# ADC.net
KiCad netlist of a schematic drawn in Altium Designer
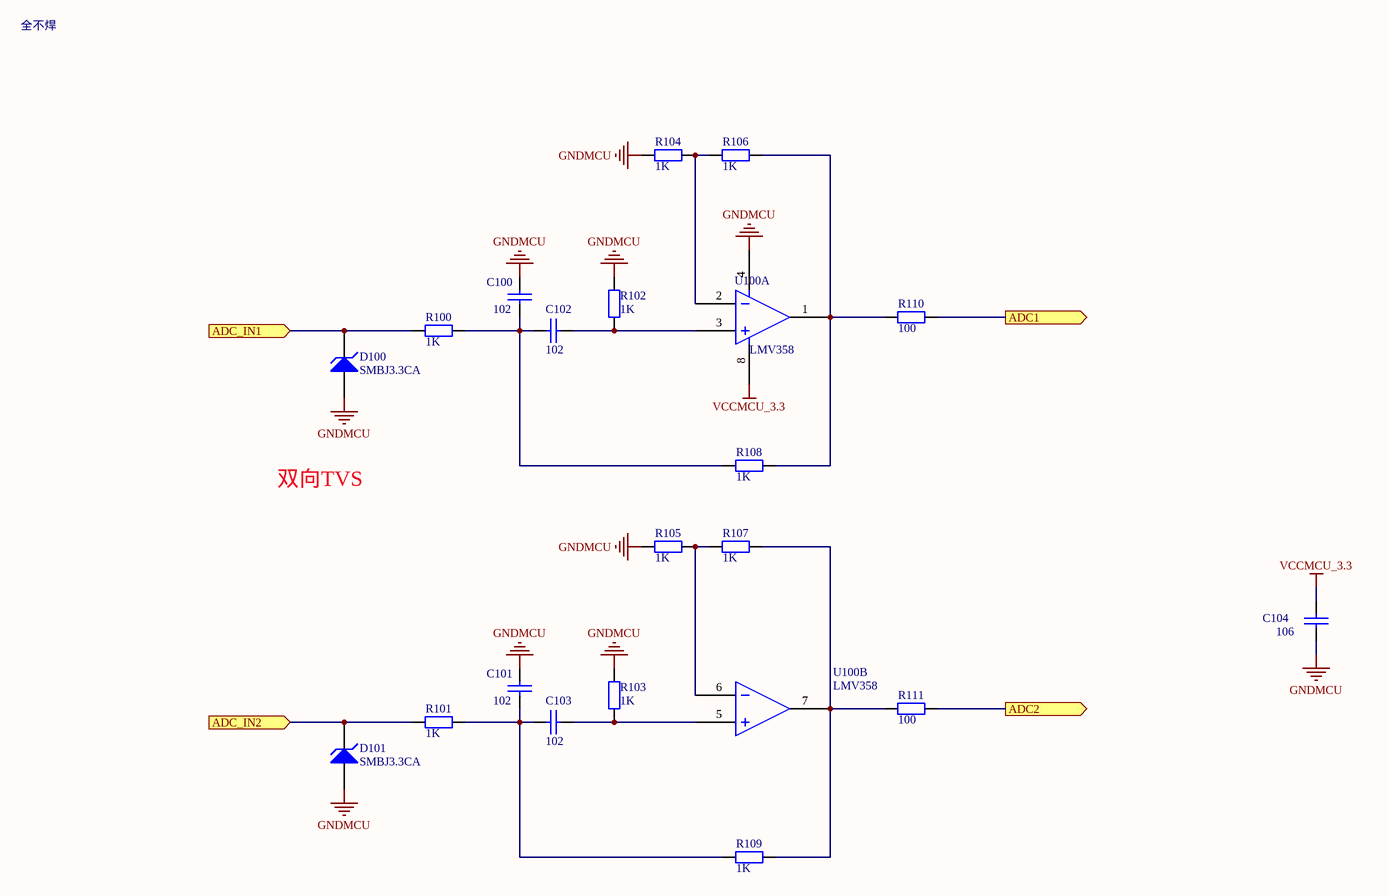
[diagram p0: ADC.SchDoc]

(export (version "E")
  (design (tool "Eeschema 10.0.6"))
  (components
    (comp (ref "C100")
      (value "102")
      (footprint "0805/C2")
      (description "Capacitor")
      (libsource (lib "YGInfoSCHLib") (part "CAP"))
    )
    (comp (ref "C101")
      (value "102")
      (footprint "0805/C2")
      (description "Capacitor")
      (libsource (lib "YGInfoSCHLib") (part "CAP"))
    )
    (comp (ref "C102")
      (value "102")
      (footprint "0805/C2")
      (description "Capacitor")
      (libsource (lib "YGInfoSCHLib") (part "CAP"))
    )
    (comp (ref "C103")
      (value "102")
      (footprint "0805/C2")
      (description "Capacitor")
      (libsource (lib "YGInfoSCHLib") (part "CAP"))
    )
    (comp (ref "C104")
      (value "106")
      (footprint "0805/C2")
      (description "Capacitor")
      (libsource (lib "YGInfoSCHLib") (part "CAP"))
    )
    (comp (ref "D100")
      (value "SMBJ3.3CA")
      (footprint "SMB")
      (description "Zener Diode")
      (fields (field (name "PUBLISHER") "Altium Limited"))
      (libsource (lib "YGInfoSCHLib") (part "D Zener"))
    )
    (comp (ref "D101")
      (value "SMBJ3.3CA")
      (footprint "SMB")
      (description "Zener Diode")
      (fields (field (name "PUBLISHER") "Altium Limited"))
      (libsource (lib "YGInfoSCHLib") (part "D Zener"))
    )
    (comp (ref "R100") (value "1K") (footprint "0805/R2") (libsource (lib "") (part "RES1_2")))
    (comp (ref "R101") (value "1K") (footprint "0805/R2") (libsource (lib "") (part "RES1_2")))
    (comp (ref "R102") (value "1K") (footprint "0805/R2") (libsource (lib "YGInfoSCHLib") (part "RES1")))
    (comp (ref "R103") (value "1K") (footprint "0805/R2") (libsource (lib "YGInfoSCHLib") (part "RES1")))
    (comp (ref "R104") (value "1K") (footprint "0805/R2") (libsource (lib "") (part "RES1_1")))
    (comp (ref "R105") (value "1K") (footprint "0805/R2") (libsource (lib "") (part "RES1_1")))
    (comp (ref "R106") (value "1K") (footprint "0805/R2") (libsource (lib "") (part "RES1_2")))
    (comp (ref "R107") (value "1K") (footprint "0805/R2") (libsource (lib "") (part "RES1_2")))
    (comp (ref "R108") (value "1K") (footprint "0805/R2") (libsource (lib "") (part "RES1_2")))
    (comp (ref "R109") (value "1K") (footprint "0805/R2") (libsource (lib "") (part "RES1_2")))
    (comp (ref "R110") (value "100") (footprint "0805/R2") (libsource (lib "") (part "RES1_2")))
    (comp (ref "R111") (value "100") (footprint "0805/R2") (libsource (lib "") (part "RES1_2")))
    (comp (ref "U100") (value "LMV358") (footprint "SO-8") (libsource (lib "YGInfoSCHLib") (part "1458")))
  )
  (nets
    (net (code "1") (name "/ADC1") (class "Default")
      (node (ref "R110") (pin "1") (pinfunction "1_1") (pintype "passive"))
    )
    (net (code "2") (name "/ADC2") (class "Default")
      (node (ref "R111") (pin "1") (pinfunction "1_1") (pintype "passive"))
    )
    (net (code "3") (name "/ADC_IN1") (class "Default")
      (node (ref "D100") (pin "2") (pinfunction "K_2") (pintype "passive"))
      (node (ref "R100") (pin "2") (pinfunction "2_2") (pintype "passive"))
    )
    (net (code "4") (name "/ADC_IN2") (class "Default")
      (node (ref "D101") (pin "2") (pinfunction "K_2") (pintype "passive"))
      (node (ref "R101") (pin "2") (pinfunction "2_2") (pintype "passive"))
    )
    (net (code "5") (name "GNDMCU") (class "Default")
      (node (ref "C100") (pin "1") (pinfunction "1_1") (pintype "passive"))
      (node (ref "C101") (pin "1") (pinfunction "1_1") (pintype "passive"))
      (node (ref "C104") (pin "2") (pinfunction "2_2") (pintype "passive"))
      (node (ref "D100") (pin "1") (pinfunction "A_1") (pintype "passive"))
      (node (ref "D101") (pin "1") (pinfunction "A_1") (pintype "passive"))
      (node (ref "R102") (pin "1") (pinfunction "1_1") (pintype "passive"))
      (node (ref "R103") (pin "1") (pinfunction "1_1") (pintype "passive"))
      (node (ref "R104") (pin "1") (pinfunction "1_1") (pintype "passive"))
      (node (ref "R105") (pin "1") (pinfunction "1_1") (pintype "passive"))
      (node (ref "U100") (pin "4") (pintype "passive"))
    )
    (net (code "6") (name "Net-(C100-Pad2)") (class "Default")
      (node (ref "C100") (pin "2") (pinfunction "2_2") (pintype "passive"))
      (node (ref "C102") (pin "1") (pinfunction "1_1") (pintype "passive"))
      (node (ref "R100") (pin "1") (pinfunction "1_1") (pintype "passive"))
      (node (ref "R108") (pin "2") (pinfunction "2_2") (pintype "passive"))
    )
    (net (code "7") (name "Net-(C101-Pad2)") (class "Default")
      (node (ref "C101") (pin "2") (pinfunction "2_2") (pintype "passive"))
      (node (ref "C103") (pin "1") (pinfunction "1_1") (pintype "passive"))
      (node (ref "R101") (pin "1") (pinfunction "1_1") (pintype "passive"))
      (node (ref "R109") (pin "2") (pinfunction "2_2") (pintype "passive"))
    )
    (net (code "8") (name "Net-(C102-Pad2)") (class "Default")
      (node (ref "C102") (pin "2") (pinfunction "2_2") (pintype "passive"))
      (node (ref "R102") (pin "2") (pinfunction "2_2") (pintype "passive"))
      (node (ref "U100") (pin "3") (pintype "passive"))
    )
    (net (code "9") (name "Net-(C103-Pad2)") (class "Default")
      (node (ref "C103") (pin "2") (pinfunction "2_2") (pintype "passive"))
      (node (ref "R103") (pin "2") (pinfunction "2_2") (pintype "passive"))
      (node (ref "U100") (pin "5") (pintype "passive"))
    )
    (net (code "10") (name "Net-(R104-Pad2)") (class "Default")
      (node (ref "R104") (pin "2") (pinfunction "2_2") (pintype "passive"))
      (node (ref "R106") (pin "2") (pinfunction "2_2") (pintype "passive"))
      (node (ref "U100") (pin "2") (pintype "passive"))
    )
    (net (code "11") (name "Net-(R105-Pad2)") (class "Default")
      (node (ref "R105") (pin "2") (pinfunction "2_2") (pintype "passive"))
      (node (ref "R107") (pin "2") (pinfunction "2_2") (pintype "passive"))
      (node (ref "U100") (pin "6") (pintype "passive"))
    )
    (net (code "12") (name "Net-(R106-Pad1)") (class "Default")
      (node (ref "R106") (pin "1") (pinfunction "1_1") (pintype "passive"))
      (node (ref "R108") (pin "1") (pinfunction "1_1") (pintype "passive"))
      (node (ref "R110") (pin "2") (pinfunction "2_2") (pintype "passive"))
      (node (ref "U100") (pin "1") (pintype "passive"))
    )
    (net (code "13") (name "Net-(R107-Pad1)") (class "Default")
      (node (ref "R107") (pin "1") (pinfunction "1_1") (pintype "passive"))
      (node (ref "R109") (pin "1") (pinfunction "1_1") (pintype "passive"))
      (node (ref "R111") (pin "2") (pinfunction "2_2") (pintype "passive"))
      (node (ref "U100") (pin "7") (pintype "passive"))
    )
    (net (code "14") (name "VCCMCU_3.3") (class "Default")
      (node (ref "C104") (pin "1") (pinfunction "1_1") (pintype "passive"))
      (node (ref "U100") (pin "8") (pintype "passive"))
    )
  )
)
